# roten.net
KiCad netlist of a schematic drawn in EAGLE
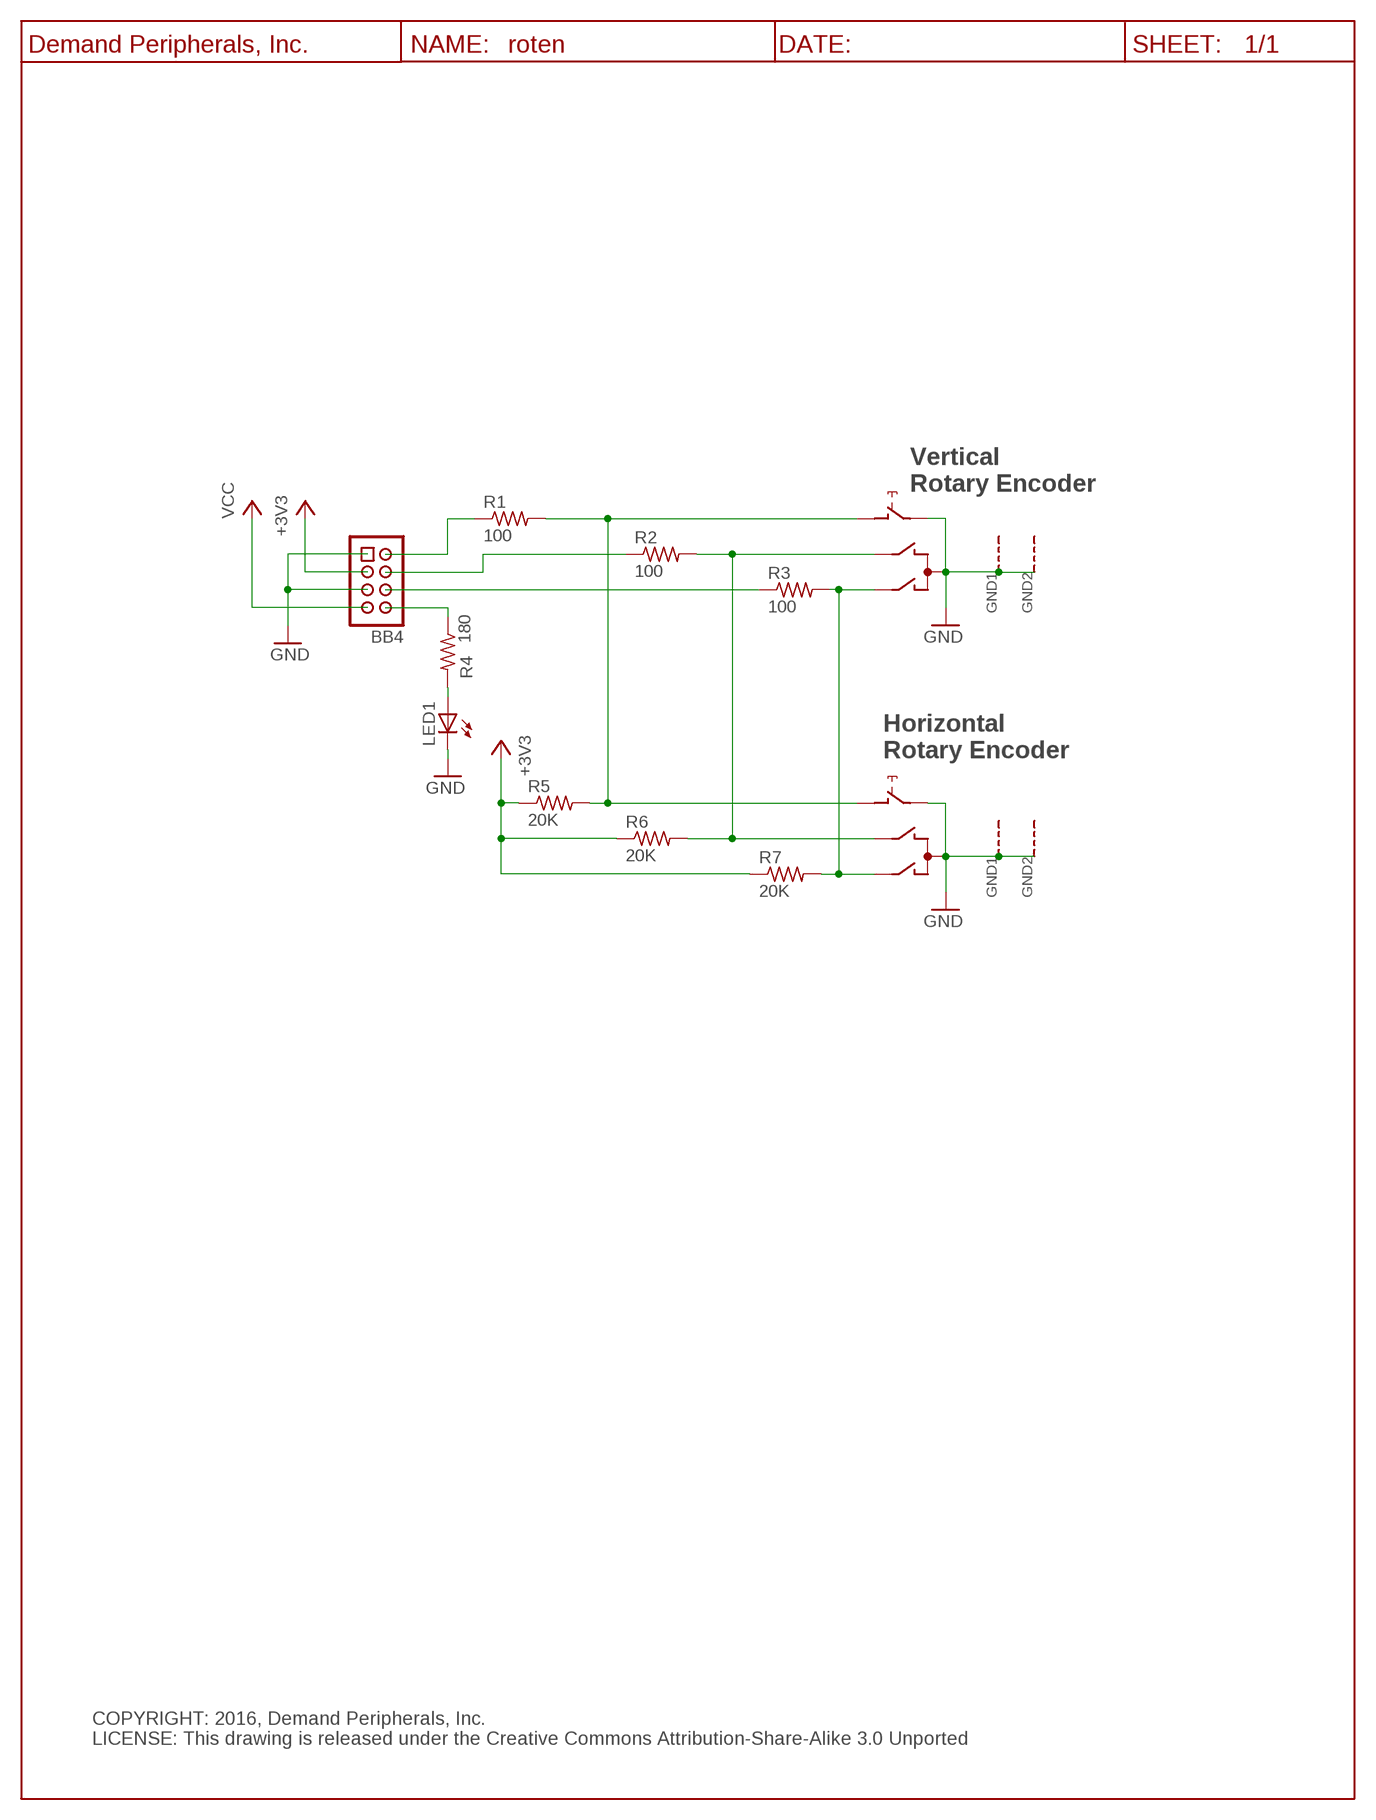
[diagram p0: schematic, sheet 1]

(export (version "E")
  (design (tool "Eeschema 10.0.6"))
  (components
    (comp (ref "1")
      (value "ROTARY_ENCODER_W_SWITCHCTS_V_120")
      (footprint "eagle-import:CTS_290_VERT")
      (libsource (lib "eagle-import") (part "ROTARY_ENCODER_W_SWITCHCTS_V_290"))
    )
    (comp (ref "2")
      (value "ROTARY_ENCODER_W_SWITCH")
      (footprint "eagle-import:BI_EN11_HORIZ")
      (libsource (lib "eagle-import") (part "ROTARY_ENCODER_W_SWITCH"))
    )
    (comp (ref "BB4")
      (value "HDR-4X2-SHR")
      (footprint "eagle-import:HDR-4X2")
      (libsource (lib "eagle-import") (part "HDR-4X2-SHR"))
    )
    (comp (ref "LED1")
      (value "LED-5MM-GRN")
      (footprint "eagle-import:LED5MM")
      (libsource (lib "eagle-import") (part "LED-5MM-GRN"))
    )
    (comp (ref "R1")
      (value "100")
      (footprint "eagle-import:R0603")
      (libsource (lib "eagle-import") (part "R100_R0603"))
    )
    (comp (ref "R2")
      (value "100")
      (footprint "eagle-import:R0603")
      (libsource (lib "eagle-import") (part "R100_R0603"))
    )
    (comp (ref "R3")
      (value "100")
      (footprint "eagle-import:R0603")
      (libsource (lib "eagle-import") (part "R100_R0603"))
    )
    (comp (ref "R4")
      (value "180")
      (footprint "eagle-import:R0603")
      (libsource (lib "eagle-import") (part "R220_R0603"))
    )
    (comp (ref "R5")
      (value "20K")
      (footprint "eagle-import:R0603")
      (libsource (lib "eagle-import") (part "R20K_R0603"))
    )
    (comp (ref "R6")
      (value "20K")
      (footprint "eagle-import:R0603")
      (libsource (lib "eagle-import") (part "R20K_R0603"))
    )
    (comp (ref "R7")
      (value "20K")
      (footprint "eagle-import:R0603")
      (libsource (lib "eagle-import") (part "R20K_R0603"))
    )
    (comp (ref "U$1")
      (value "DP_FRAME_P")
      (footprint "eagle-import:P_FRAME")
      (libsource (lib "eagle-import") (part "DP_FRAME_P"))
    )
  )
  (nets
    (net (code "1") (name "+3V3") (class "Default")
      (node (ref "BB4") (pin "3") (pinfunction "3_3") (pintype "passive"))
      (node (ref "R5") (pin "1") (pinfunction "1_1") (pintype "passive"))
      (node (ref "R6") (pin "1") (pinfunction "1_1") (pintype "passive"))
      (node (ref "R7") (pin "1") (pinfunction "1_1") (pintype "passive"))
    )
    (net (code "2") (name "GND") (class "Default")
      (node (ref "1") (pin "C") (pinfunction "C_C") (pintype "passive"))
      (node (ref "1") (pin "E") (pinfunction "E_E") (pintype "passive"))
      (node (ref "1") (pin "GND1") (pinfunction "G_GND1") (pintype "passive"))
      (node (ref "1") (pin "GND2") (pinfunction "G_GND2") (pintype "passive"))
      (node (ref "2") (pin "C") (pinfunction "C_C") (pintype "passive"))
      (node (ref "2") (pin "E") (pinfunction "E_E") (pintype "passive"))
      (node (ref "2") (pin "GND1") (pinfunction "G_GND1") (pintype "passive"))
      (node (ref "2") (pin "GND2") (pinfunction "G_GND2") (pintype "passive"))
      (node (ref "BB4") (pin "1") (pinfunction "1_1") (pintype "passive"))
      (node (ref "BB4") (pin "5") (pinfunction "5_5") (pintype "passive"))
      (node (ref "LED1") (pin "C") (pinfunction "C_C") (pintype "passive"))
    )
    (net (code "3") (name "Net-(1-PadA)") (class "Default")
      (node (ref "1") (pin "A") (pinfunction "A_A") (pintype "passive"))
      (node (ref "2") (pin "A") (pinfunction "A_A") (pintype "passive"))
      (node (ref "R3") (pin "2") (pinfunction "2_2") (pintype "passive"))
      (node (ref "R7") (pin "2") (pinfunction "2_2") (pintype "passive"))
    )
    (net (code "4") (name "Net-(1-PadB)") (class "Default")
      (node (ref "1") (pin "B") (pinfunction "B_B") (pintype "passive"))
      (node (ref "2") (pin "B") (pinfunction "B_B") (pintype "passive"))
      (node (ref "R2") (pin "2") (pinfunction "2_2") (pintype "passive"))
      (node (ref "R6") (pin "2") (pinfunction "2_2") (pintype "passive"))
    )
    (net (code "5") (name "Net-(1-PadD)") (class "Default")
      (node (ref "1") (pin "D") (pinfunction "D_D") (pintype "passive"))
      (node (ref "2") (pin "D") (pinfunction "D_D") (pintype "passive"))
      (node (ref "R1") (pin "2") (pinfunction "2_2") (pintype "passive"))
      (node (ref "R5") (pin "2") (pinfunction "2_2") (pintype "passive"))
    )
    (net (code "6") (name "Net-(BB4-Pad2)") (class "Default")
      (node (ref "BB4") (pin "2") (pinfunction "2_2") (pintype "passive"))
      (node (ref "R1") (pin "1") (pinfunction "1_1") (pintype "passive"))
    )
    (net (code "7") (name "Net-(BB4-Pad4)") (class "Default")
      (node (ref "BB4") (pin "4") (pinfunction "4_4") (pintype "passive"))
      (node (ref "R2") (pin "1") (pinfunction "1_1") (pintype "passive"))
    )
    (net (code "8") (name "Net-(BB4-Pad6)") (class "Default")
      (node (ref "BB4") (pin "6") (pinfunction "6_6") (pintype "passive"))
      (node (ref "R3") (pin "1") (pinfunction "1_1") (pintype "passive"))
    )
    (net (code "9") (name "Net-(BB4-Pad8)") (class "Default")
      (node (ref "BB4") (pin "8") (pinfunction "8_8") (pintype "passive"))
      (node (ref "R4") (pin "1") (pinfunction "1_1") (pintype "passive"))
    )
    (net (code "10") (name "Net-(LED1-PadA)") (class "Default")
      (node (ref "LED1") (pin "A") (pinfunction "A_A") (pintype "passive"))
      (node (ref "R4") (pin "2") (pinfunction "2_2") (pintype "passive"))
    )
    (net (code "11") (name "VCC") (class "Default")
      (node (ref "BB4") (pin "7") (pinfunction "7_7") (pintype "passive"))
    )
  )
)
